# dual_vca_main.net
KiCad netlist of a schematic drawn in EAGLE
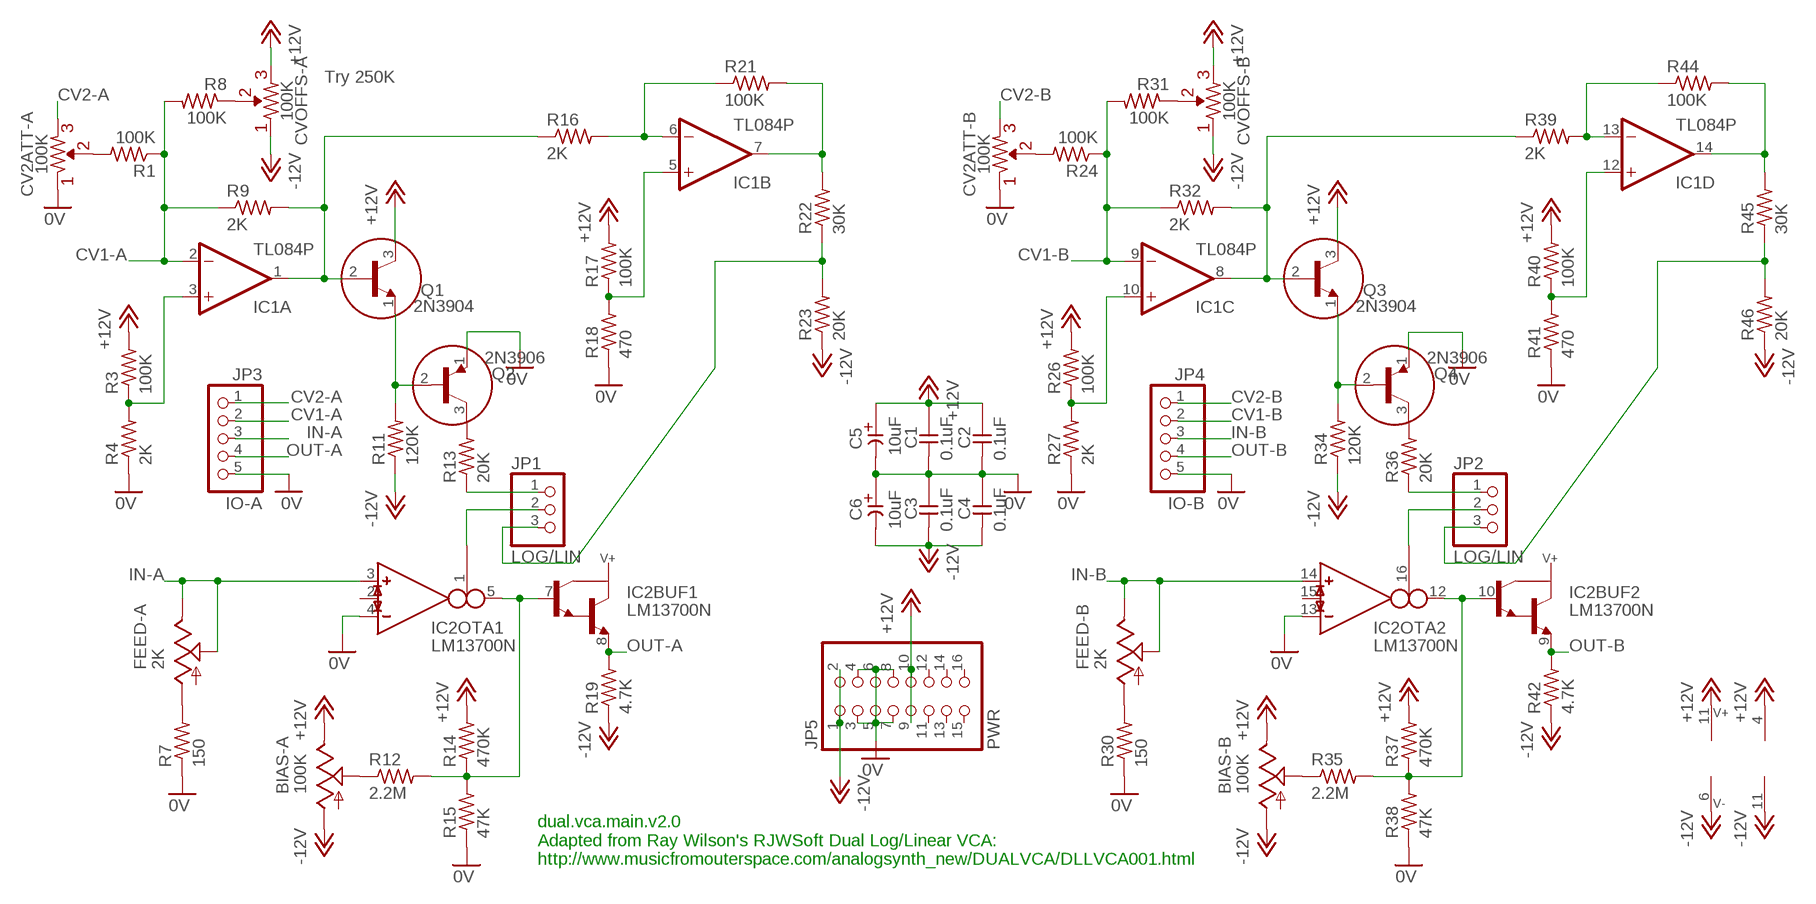
[diagram p0: schematic, sheet 1]

(export (version "E")
  (design (tool "Eeschema 10.0.6"))
  (components
    (comp (ref "BIAS-A")
      (value "100K")
      (footprint "eagle-import:PT-10S")
      (libsource (lib "eagle-import") (part "TRIM_US-PT10S"))
    )
    (comp (ref "BIAS-B")
      (value "100K")
      (footprint "eagle-import:PT-10S")
      (libsource (lib "eagle-import") (part "TRIM_US-PT10S"))
    )
    (comp (ref "C1")
      (value "0.1uF")
      (footprint "eagle-import:C025-024X044")
      (libsource (lib "eagle-import") (part "CC-US025-024X044"))
    )
    (comp (ref "C2")
      (value "0.1uF")
      (footprint "eagle-import:C025-024X044")
      (libsource (lib "eagle-import") (part "CC-US025-024X044"))
    )
    (comp (ref "C3")
      (value "0.1uF")
      (footprint "eagle-import:C025-024X044")
      (libsource (lib "eagle-import") (part "CC-US025-024X044"))
    )
    (comp (ref "C4")
      (value "0.1uF")
      (footprint "eagle-import:C025-024X044")
      (libsource (lib "eagle-import") (part "CC-US025-024X044"))
    )
    (comp (ref "C5")
      (value "10uF")
      (footprint "eagle-import:E2-5")
      (libsource (lib "eagle-import") (part "CE-USE2-5"))
    )
    (comp (ref "C6")
      (value "10uF")
      (footprint "eagle-import:E2-5")
      (libsource (lib "eagle-import") (part "CE-USE2-5"))
    )
    (comp (ref "CV2ATT-A")
      (value "100K")
      (footprint "eagle-import:R-VAR")
      (libsource (lib "eagle-import") (part "R-VAR"))
    )
    (comp (ref "CV2ATT-B")
      (value "100K")
      (footprint "eagle-import:R-VAR")
      (libsource (lib "eagle-import") (part "R-VAR"))
    )
    (comp (ref "CVOFFS-A")
      (value "100K")
      (footprint "eagle-import:R-VAR")
      (libsource (lib "eagle-import") (part "R-VAR"))
    )
    (comp (ref "CVOFFS-B")
      (value "100K")
      (footprint "eagle-import:R-VAR")
      (libsource (lib "eagle-import") (part "R-VAR"))
    )
    (comp (ref "FEED-A")
      (value "2K")
      (footprint "eagle-import:PT-10S")
      (libsource (lib "eagle-import") (part "TRIM_US-PT10S"))
    )
    (comp (ref "FEED-B")
      (value "2K")
      (footprint "eagle-import:PT-10S")
      (libsource (lib "eagle-import") (part "TRIM_US-PT10S"))
    )
    (comp (ref "IC1")
      (value "TL084P")
      (footprint "eagle-import:DIL14")
      (libsource (lib "eagle-import") (part "TL084P"))
    )
    (comp (ref "IC2")
      (value "LM13700N")
      (footprint "eagle-import:DIL16")
      (libsource (lib "eagle-import") (part "LM13700N"))
    )
    (comp (ref "JP1")
      (value "LOG/LIN")
      (footprint "eagle-import:1X03")
      (libsource (lib "eagle-import") (part "PINHD-1X3"))
    )
    (comp (ref "JP2")
      (value "LOG/LIN")
      (footprint "eagle-import:1X03")
      (libsource (lib "eagle-import") (part "PINHD-1X3"))
    )
    (comp (ref "JP3")
      (value "IO-A")
      (footprint "eagle-import:1X05")
      (libsource (lib "eagle-import") (part "PINHD-1X5"))
    )
    (comp (ref "JP4")
      (value "IO-B")
      (footprint "eagle-import:1X05")
      (libsource (lib "eagle-import") (part "PINHD-1X5"))
    )
    (comp (ref "JP5")
      (value "PWR")
      (footprint "eagle-import:2X08")
      (libsource (lib "eagle-import") (part "PINHD-2X8"))
    )
    (comp (ref "Q1")
      (value "2N3904")
      (footprint "eagle-import:TO92")
      (libsource (lib "eagle-import") (part "2N3904"))
    )
    (comp (ref "Q2")
      (value "2N3906")
      (footprint "eagle-import:TO92")
      (libsource (lib "eagle-import") (part "2N3906"))
    )
    (comp (ref "Q3")
      (value "2N3904")
      (footprint "eagle-import:TO92")
      (libsource (lib "eagle-import") (part "2N3904"))
    )
    (comp (ref "Q4")
      (value "2N3906")
      (footprint "eagle-import:TO92")
      (libsource (lib "eagle-import") (part "2N3906"))
    )
    (comp (ref "R1")
      (value "100K")
      (footprint "eagle-import:0207_7")
      (libsource (lib "eagle-import") (part "R-US_0207/7"))
    )
    (comp (ref "R3")
      (value "100K")
      (footprint "eagle-import:0207_7")
      (libsource (lib "eagle-import") (part "R-US_0207/7"))
    )
    (comp (ref "R4")
      (value "2K")
      (footprint "eagle-import:0207_7")
      (libsource (lib "eagle-import") (part "R-US_0207/7"))
    )
    (comp (ref "R7")
      (value "150")
      (footprint "eagle-import:0207_7")
      (libsource (lib "eagle-import") (part "R-US_0207/7"))
    )
    (comp (ref "R8")
      (value "100K")
      (footprint "eagle-import:0207_7")
      (libsource (lib "eagle-import") (part "R-US_0207/7"))
    )
    (comp (ref "R9")
      (value "2K")
      (footprint "eagle-import:0207_7")
      (libsource (lib "eagle-import") (part "R-US_0207/7"))
    )
    (comp (ref "R11")
      (value "120K")
      (footprint "eagle-import:0207_7")
      (libsource (lib "eagle-import") (part "R-US_0207/7"))
    )
    (comp (ref "R12")
      (value "2.2M")
      (footprint "eagle-import:0207_7")
      (libsource (lib "eagle-import") (part "R-US_0207/7"))
    )
    (comp (ref "R13")
      (value "20K")
      (footprint "eagle-import:0207_7")
      (libsource (lib "eagle-import") (part "R-US_0207/7"))
    )
    (comp (ref "R14")
      (value "470K")
      (footprint "eagle-import:0207_7")
      (libsource (lib "eagle-import") (part "R-US_0207/7"))
    )
    (comp (ref "R15")
      (value "47K")
      (footprint "eagle-import:0207_7")
      (libsource (lib "eagle-import") (part "R-US_0207/7"))
    )
    (comp (ref "R16")
      (value "2K")
      (footprint "eagle-import:0207_7")
      (libsource (lib "eagle-import") (part "R-US_0207/7"))
    )
    (comp (ref "R17")
      (value "100K")
      (footprint "eagle-import:0207_7")
      (libsource (lib "eagle-import") (part "R-US_0207/7"))
    )
    (comp (ref "R18")
      (value "470")
      (footprint "eagle-import:0207_7")
      (libsource (lib "eagle-import") (part "R-US_0207/7"))
    )
    (comp (ref "R19")
      (value "4.7K")
      (footprint "eagle-import:0207_7")
      (libsource (lib "eagle-import") (part "R-US_0207/7"))
    )
    (comp (ref "R21")
      (value "100K")
      (footprint "eagle-import:0207_7")
      (libsource (lib "eagle-import") (part "R-US_0207/7"))
    )
    (comp (ref "R22")
      (value "30K")
      (footprint "eagle-import:0207_7")
      (libsource (lib "eagle-import") (part "R-US_0207/7"))
    )
    (comp (ref "R23")
      (value "20K")
      (footprint "eagle-import:0207_7")
      (libsource (lib "eagle-import") (part "R-US_0207/7"))
    )
    (comp (ref "R24")
      (value "100K")
      (footprint "eagle-import:0207_7")
      (libsource (lib "eagle-import") (part "R-US_0207/7"))
    )
    (comp (ref "R26")
      (value "100K")
      (footprint "eagle-import:0207_7")
      (libsource (lib "eagle-import") (part "R-US_0207/7"))
    )
    (comp (ref "R27")
      (value "2K")
      (footprint "eagle-import:0207_7")
      (libsource (lib "eagle-import") (part "R-US_0207/7"))
    )
    (comp (ref "R30")
      (value "150")
      (footprint "eagle-import:0207_7")
      (libsource (lib "eagle-import") (part "R-US_0207/7"))
    )
    (comp (ref "R31")
      (value "100K")
      (footprint "eagle-import:0207_7")
      (libsource (lib "eagle-import") (part "R-US_0207/7"))
    )
    (comp (ref "R32")
      (value "2K")
      (footprint "eagle-import:0207_7")
      (libsource (lib "eagle-import") (part "R-US_0207/7"))
    )
    (comp (ref "R34")
      (value "120K")
      (footprint "eagle-import:0207_7")
      (libsource (lib "eagle-import") (part "R-US_0207/7"))
    )
    (comp (ref "R35")
      (value "2.2M")
      (footprint "eagle-import:0207_7")
      (libsource (lib "eagle-import") (part "R-US_0207/7"))
    )
    (comp (ref "R36")
      (value "20K")
      (footprint "eagle-import:0207_7")
      (libsource (lib "eagle-import") (part "R-US_0207/7"))
    )
    (comp (ref "R37")
      (value "470K")
      (footprint "eagle-import:0207_7")
      (libsource (lib "eagle-import") (part "R-US_0207/7"))
    )
    (comp (ref "R38")
      (value "47K")
      (footprint "eagle-import:0207_7")
      (libsource (lib "eagle-import") (part "R-US_0207/7"))
    )
    (comp (ref "R39")
      (value "2K")
      (footprint "eagle-import:0207_7")
      (libsource (lib "eagle-import") (part "R-US_0207/7"))
    )
    (comp (ref "R40")
      (value "100K")
      (footprint "eagle-import:0207_7")
      (libsource (lib "eagle-import") (part "R-US_0207/7"))
    )
    (comp (ref "R41")
      (value "470")
      (footprint "eagle-import:0207_7")
      (libsource (lib "eagle-import") (part "R-US_0207/7"))
    )
    (comp (ref "R42")
      (value "4.7K")
      (footprint "eagle-import:0207_7")
      (libsource (lib "eagle-import") (part "R-US_0207/7"))
    )
    (comp (ref "R44")
      (value "100K")
      (footprint "eagle-import:0207_7")
      (libsource (lib "eagle-import") (part "R-US_0207/7"))
    )
    (comp (ref "R45")
      (value "30K")
      (footprint "eagle-import:0207_7")
      (libsource (lib "eagle-import") (part "R-US_0207/7"))
    )
    (comp (ref "R46")
      (value "20K")
      (footprint "eagle-import:0207_7")
      (libsource (lib "eagle-import") (part "R-US_0207/7"))
    )
  )
  (nets
    (net (code "1") (name "+12V") (class "Default")
      (node (ref "BIAS-A") (pin "E") (pinfunction "E_E") (pintype "passive"))
      (node (ref "BIAS-B") (pin "E") (pinfunction "E_E") (pintype "passive"))
      (node (ref "C1") (pin "1") (pinfunction "1_1") (pintype "passive"))
      (node (ref "C2") (pin "1") (pinfunction "1_1") (pintype "passive"))
      (node (ref "C5") (pin "+") (pinfunction "+_+") (pintype "passive"))
      (node (ref "CVOFFS-A") (pin "R2") (pinfunction "2_R2") (pintype "passive"))
      (node (ref "CVOFFS-B") (pin "R2") (pinfunction "2_R2") (pintype "passive"))
      (node (ref "IC1") (pin "4") (pinfunction "V+_4") (pintype "power_in"))
      (node (ref "IC2") (pin "11") (pinfunction "V+_11") (pintype "power_in"))
      (node (ref "JP5") (pin "10") (pinfunction "10_10") (pintype "passive"))
      (node (ref "JP5") (pin "9") (pinfunction "9_9") (pintype "passive"))
      (node (ref "Q1") (pin "3") (pinfunction "C_3") (pintype "passive"))
      (node (ref "Q3") (pin "3") (pinfunction "C_3") (pintype "passive"))
      (node (ref "R14") (pin "2") (pinfunction "2_2") (pintype "passive"))
      (node (ref "R17") (pin "2") (pinfunction "2_2") (pintype "passive"))
      (node (ref "R26") (pin "2") (pinfunction "2_2") (pintype "passive"))
      (node (ref "R3") (pin "2") (pinfunction "2_2") (pintype "passive"))
      (node (ref "R37") (pin "2") (pinfunction "2_2") (pintype "passive"))
      (node (ref "R40") (pin "2") (pinfunction "2_2") (pintype "passive"))
    )
    (net (code "2") (name "-12V") (class "Default")
      (node (ref "BIAS-A") (pin "A") (pinfunction "A_A") (pintype "passive"))
      (node (ref "BIAS-B") (pin "A") (pinfunction "A_A") (pintype "passive"))
      (node (ref "C3") (pin "2") (pinfunction "2_2") (pintype "passive"))
      (node (ref "C4") (pin "2") (pinfunction "2_2") (pintype "passive"))
      (node (ref "C6") (pin "-") (pinfunction "-_-") (pintype "passive"))
      (node (ref "CVOFFS-A") (pin "R1") (pinfunction "1_R1") (pintype "passive"))
      (node (ref "CVOFFS-B") (pin "R1") (pinfunction "1_R1") (pintype "passive"))
      (node (ref "IC1") (pin "11") (pinfunction "V-_11") (pintype "power_in"))
      (node (ref "IC2") (pin "6") (pinfunction "V-_6") (pintype "power_in"))
      (node (ref "JP5") (pin "1") (pinfunction "1_1") (pintype "passive"))
      (node (ref "JP5") (pin "2") (pinfunction "2_2") (pintype "passive"))
      (node (ref "R11") (pin "1") (pinfunction "1_1") (pintype "passive"))
      (node (ref "R19") (pin "1") (pinfunction "1_1") (pintype "passive"))
      (node (ref "R23") (pin "1") (pinfunction "1_1") (pintype "passive"))
      (node (ref "R34") (pin "1") (pinfunction "1_1") (pintype "passive"))
      (node (ref "R42") (pin "1") (pinfunction "1_1") (pintype "passive"))
      (node (ref "R46") (pin "1") (pinfunction "1_1") (pintype "passive"))
    )
    (net (code "3") (name "/CV1-A") (class "Default")
      (node (ref "IC1") (pin "2") (pinfunction "-IN_2") (pintype "input"))
      (node (ref "JP3") (pin "2") (pinfunction "2_2") (pintype "passive"))
      (node (ref "R1") (pin "1") (pinfunction "1_1") (pintype "passive"))
      (node (ref "R8") (pin "2") (pinfunction "2_2") (pintype "passive"))
      (node (ref "R9") (pin "1") (pinfunction "1_1") (pintype "passive"))
    )
    (net (code "4") (name "/CV1-B") (class "Default")
      (node (ref "IC1") (pin "9") (pinfunction "-IN_9") (pintype "input"))
      (node (ref "JP4") (pin "2") (pinfunction "2_2") (pintype "passive"))
      (node (ref "R24") (pin "1") (pinfunction "1_1") (pintype "passive"))
      (node (ref "R31") (pin "2") (pinfunction "2_2") (pintype "passive"))
      (node (ref "R32") (pin "1") (pinfunction "1_1") (pintype "passive"))
    )
    (net (code "5") (name "/CV2-A") (class "Default")
      (node (ref "CV2ATT-A") (pin "R2") (pinfunction "2_R2") (pintype "passive"))
      (node (ref "JP3") (pin "1") (pinfunction "1_1") (pintype "passive"))
    )
    (net (code "6") (name "/CV2-B") (class "Default")
      (node (ref "CV2ATT-B") (pin "R2") (pinfunction "2_R2") (pintype "passive"))
      (node (ref "JP4") (pin "1") (pinfunction "1_1") (pintype "passive"))
    )
    (net (code "7") (name "/IN-A") (class "Default")
      (node (ref "FEED-A") (pin "E") (pinfunction "E_E") (pintype "passive"))
      (node (ref "FEED-A") (pin "S") (pinfunction "S_S") (pintype "passive"))
      (node (ref "IC2") (pin "3") (pinfunction "IN_P_3") (pintype "input"))
      (node (ref "JP3") (pin "3") (pinfunction "3_3") (pintype "passive"))
    )
    (net (code "8") (name "/IN-B") (class "Default")
      (node (ref "FEED-B") (pin "E") (pinfunction "E_E") (pintype "passive"))
      (node (ref "FEED-B") (pin "S") (pinfunction "S_S") (pintype "passive"))
      (node (ref "IC2") (pin "14") (pinfunction "IN_P_14") (pintype "input"))
      (node (ref "JP4") (pin "3") (pinfunction "3_3") (pintype "passive"))
    )
    (net (code "9") (name "/OUT-A") (class "Default")
      (node (ref "IC2") (pin "8") (pinfunction "E_8") (pintype "passive"))
      (node (ref "JP3") (pin "4") (pinfunction "4_4") (pintype "passive"))
      (node (ref "R19") (pin "2") (pinfunction "2_2") (pintype "passive"))
    )
    (net (code "10") (name "/OUT-B") (class "Default")
      (node (ref "IC2") (pin "9") (pinfunction "E_9") (pintype "passive"))
      (node (ref "JP4") (pin "4") (pinfunction "4_4") (pintype "passive"))
      (node (ref "R42") (pin "2") (pinfunction "2_2") (pintype "passive"))
    )
    (net (code "11") (name "0V") (class "Default")
      (node (ref "C1") (pin "2") (pinfunction "2_2") (pintype "passive"))
      (node (ref "C2") (pin "2") (pinfunction "2_2") (pintype "passive"))
      (node (ref "C3") (pin "1") (pinfunction "1_1") (pintype "passive"))
      (node (ref "C4") (pin "1") (pinfunction "1_1") (pintype "passive"))
      (node (ref "C5") (pin "-") (pinfunction "-_-") (pintype "passive"))
      (node (ref "C6") (pin "+") (pinfunction "+_+") (pintype "passive"))
      (node (ref "CV2ATT-A") (pin "R1") (pinfunction "1_R1") (pintype "passive"))
      (node (ref "CV2ATT-B") (pin "R1") (pinfunction "1_R1") (pintype "passive"))
      (node (ref "IC2") (pin "13") (pinfunction "IN_N_13") (pintype "input"))
      (node (ref "IC2") (pin "4") (pinfunction "IN_N_4") (pintype "input"))
      (node (ref "JP3") (pin "5") (pinfunction "5_5") (pintype "passive"))
      (node (ref "JP4") (pin "5") (pinfunction "5_5") (pintype "passive"))
      (node (ref "JP5") (pin "3") (pinfunction "3_3") (pintype "passive"))
      (node (ref "JP5") (pin "4") (pinfunction "4_4") (pintype "passive"))
      (node (ref "JP5") (pin "5") (pinfunction "5_5") (pintype "passive"))
      (node (ref "JP5") (pin "6") (pinfunction "6_6") (pintype "passive"))
      (node (ref "JP5") (pin "7") (pinfunction "7_7") (pintype "passive"))
      (node (ref "JP5") (pin "8") (pinfunction "8_8") (pintype "passive"))
      (node (ref "Q2") (pin "1") (pinfunction "E_1") (pintype "passive"))
      (node (ref "Q4") (pin "1") (pinfunction "E_1") (pintype "passive"))
      (node (ref "R15") (pin "1") (pinfunction "1_1") (pintype "passive"))
      (node (ref "R18") (pin "1") (pinfunction "1_1") (pintype "passive"))
      (node (ref "R27") (pin "1") (pinfunction "1_1") (pintype "passive"))
      (node (ref "R30") (pin "1") (pinfunction "1_1") (pintype "passive"))
      (node (ref "R38") (pin "1") (pinfunction "1_1") (pintype "passive"))
      (node (ref "R4") (pin "1") (pinfunction "1_1") (pintype "passive"))
      (node (ref "R41") (pin "1") (pinfunction "1_1") (pintype "passive"))
      (node (ref "R7") (pin "1") (pinfunction "1_1") (pintype "passive"))
    )
    (net (code "12") (name "Net-(BIAS-A-PadS)") (class "Default")
      (node (ref "BIAS-A") (pin "S") (pinfunction "S_S") (pintype "passive"))
      (node (ref "R12") (pin "1") (pinfunction "1_1") (pintype "passive"))
    )
    (net (code "13") (name "Net-(BIAS-B-PadS)") (class "Default")
      (node (ref "BIAS-B") (pin "S") (pinfunction "S_S") (pintype "passive"))
      (node (ref "R35") (pin "1") (pinfunction "1_1") (pintype "passive"))
    )
    (net (code "14") (name "Net-(CV2ATT-A-P$1)") (class "Default")
      (node (ref "CV2ATT-A") (pin "VAR") (pinfunction "P$1_VAR") (pintype "passive"))
      (node (ref "R1") (pin "2") (pinfunction "2_2") (pintype "passive"))
    )
    (net (code "15") (name "Net-(CV2ATT-B-P$1)") (class "Default")
      (node (ref "CV2ATT-B") (pin "VAR") (pinfunction "P$1_VAR") (pintype "passive"))
      (node (ref "R24") (pin "2") (pinfunction "2_2") (pintype "passive"))
    )
    (net (code "16") (name "Net-(CVOFFS-A-P$1)") (class "Default")
      (node (ref "CVOFFS-A") (pin "VAR") (pinfunction "P$1_VAR") (pintype "passive"))
      (node (ref "R8") (pin "1") (pinfunction "1_1") (pintype "passive"))
    )
    (net (code "17") (name "Net-(CVOFFS-B-P$1)") (class "Default")
      (node (ref "CVOFFS-B") (pin "VAR") (pinfunction "P$1_VAR") (pintype "passive"))
      (node (ref "R31") (pin "1") (pinfunction "1_1") (pintype "passive"))
    )
    (net (code "18") (name "Net-(FEED-A-PadA)") (class "Default")
      (node (ref "FEED-A") (pin "A") (pinfunction "A_A") (pintype "passive"))
      (node (ref "R7") (pin "2") (pinfunction "2_2") (pintype "passive"))
    )
    (net (code "19") (name "Net-(FEED-B-PadA)") (class "Default")
      (node (ref "FEED-B") (pin "A") (pinfunction "A_A") (pintype "passive"))
      (node (ref "R30") (pin "2") (pinfunction "2_2") (pintype "passive"))
    )
    (net (code "20") (name "Net-(IC1A-+IN)") (class "Default")
      (node (ref "IC1") (pin "3") (pinfunction "+IN_3") (pintype "input"))
      (node (ref "R3") (pin "1") (pinfunction "1_1") (pintype "passive"))
      (node (ref "R4") (pin "2") (pinfunction "2_2") (pintype "passive"))
    )
    (net (code "21") (name "Net-(IC1A-OUT)") (class "Default")
      (node (ref "IC1") (pin "1") (pinfunction "OUT_1") (pintype "output"))
      (node (ref "Q1") (pin "2") (pinfunction "B_2") (pintype "passive"))
      (node (ref "R16") (pin "1") (pinfunction "1_1") (pintype "passive"))
      (node (ref "R9") (pin "2") (pinfunction "2_2") (pintype "passive"))
    )
    (net (code "22") (name "Net-(IC1B-+IN)") (class "Default")
      (node (ref "IC1") (pin "5") (pinfunction "+IN_5") (pintype "input"))
      (node (ref "R17") (pin "1") (pinfunction "1_1") (pintype "passive"))
      (node (ref "R18") (pin "2") (pinfunction "2_2") (pintype "passive"))
    )
    (net (code "23") (name "Net-(IC1B--IN)") (class "Default")
      (node (ref "IC1") (pin "6") (pinfunction "-IN_6") (pintype "input"))
      (node (ref "R16") (pin "2") (pinfunction "2_2") (pintype "passive"))
      (node (ref "R21") (pin "1") (pinfunction "1_1") (pintype "passive"))
    )
    (net (code "24") (name "Net-(IC1B-OUT)") (class "Default")
      (node (ref "IC1") (pin "7") (pinfunction "OUT_7") (pintype "output"))
      (node (ref "R21") (pin "2") (pinfunction "2_2") (pintype "passive"))
      (node (ref "R22") (pin "2") (pinfunction "2_2") (pintype "passive"))
    )
    (net (code "25") (name "Net-(IC1C-+IN)") (class "Default")
      (node (ref "IC1") (pin "10") (pinfunction "+IN_10") (pintype "input"))
      (node (ref "R26") (pin "1") (pinfunction "1_1") (pintype "passive"))
      (node (ref "R27") (pin "2") (pinfunction "2_2") (pintype "passive"))
    )
    (net (code "26") (name "Net-(IC1C-OUT)") (class "Default")
      (node (ref "IC1") (pin "8") (pinfunction "OUT_8") (pintype "output"))
      (node (ref "Q3") (pin "2") (pinfunction "B_2") (pintype "passive"))
      (node (ref "R32") (pin "2") (pinfunction "2_2") (pintype "passive"))
      (node (ref "R39") (pin "1") (pinfunction "1_1") (pintype "passive"))
    )
    (net (code "27") (name "Net-(IC1D-+IN)") (class "Default")
      (node (ref "IC1") (pin "12") (pinfunction "+IN_12") (pintype "input"))
      (node (ref "R40") (pin "1") (pinfunction "1_1") (pintype "passive"))
      (node (ref "R41") (pin "2") (pinfunction "2_2") (pintype "passive"))
    )
    (net (code "28") (name "Net-(IC1D--IN)") (class "Default")
      (node (ref "IC1") (pin "13") (pinfunction "-IN_13") (pintype "input"))
      (node (ref "R39") (pin "2") (pinfunction "2_2") (pintype "passive"))
      (node (ref "R44") (pin "1") (pinfunction "1_1") (pintype "passive"))
    )
    (net (code "29") (name "Net-(IC1D-OUT)") (class "Default")
      (node (ref "IC1") (pin "14") (pinfunction "OUT_14") (pintype "output"))
      (node (ref "R44") (pin "2") (pinfunction "2_2") (pintype "passive"))
      (node (ref "R45") (pin "2") (pinfunction "2_2") (pintype "passive"))
    )
    (net (code "30") (name "Net-(IC2A-B)") (class "Default")
      (node (ref "IC2") (pin "5") (pinfunction "OUT_5") (pintype "output"))
      (node (ref "IC2") (pin "7") (pinfunction "B_7") (pintype "passive"))
      (node (ref "R12") (pin "2") (pinfunction "2_2") (pintype "passive"))
      (node (ref "R14") (pin "1") (pinfunction "1_1") (pintype "passive"))
      (node (ref "R15") (pin "2") (pinfunction "2_2") (pintype "passive"))
    )
    (net (code "31") (name "Net-(IC2B-B)") (class "Default")
      (node (ref "IC2") (pin "10") (pinfunction "B_10") (pintype "passive"))
      (node (ref "IC2") (pin "12") (pinfunction "OUT_12") (pintype "output"))
      (node (ref "R35") (pin "2") (pinfunction "2_2") (pintype "passive"))
      (node (ref "R37") (pin "1") (pinfunction "1_1") (pintype "passive"))
      (node (ref "R38") (pin "2") (pinfunction "2_2") (pintype "passive"))
    )
    (net (code "32") (name "Net-(IC2C-I_BIAS)") (class "Default")
      (node (ref "IC2") (pin "1") (pinfunction "I_BIAS_1") (pintype "input"))
      (node (ref "JP1") (pin "2") (pinfunction "2_2") (pintype "passive"))
    )
    (net (code "33") (name "Net-(IC2D-I_BIAS)") (class "Default")
      (node (ref "IC2") (pin "16") (pinfunction "I_BIAS_16") (pintype "input"))
      (node (ref "JP2") (pin "2") (pinfunction "2_2") (pintype "passive"))
    )
    (net (code "34") (name "Net-(JP1-Pad1)") (class "Default")
      (node (ref "JP1") (pin "1") (pinfunction "1_1") (pintype "passive"))
      (node (ref "R13") (pin "1") (pinfunction "1_1") (pintype "passive"))
    )
    (net (code "35") (name "Net-(JP1-Pad3)") (class "Default")
      (node (ref "JP1") (pin "3") (pinfunction "3_3") (pintype "passive"))
      (node (ref "R22") (pin "1") (pinfunction "1_1") (pintype "passive"))
      (node (ref "R23") (pin "2") (pinfunction "2_2") (pintype "passive"))
    )
    (net (code "36") (name "Net-(JP2-Pad1)") (class "Default")
      (node (ref "JP2") (pin "1") (pinfunction "1_1") (pintype "passive"))
      (node (ref "R36") (pin "1") (pinfunction "1_1") (pintype "passive"))
    )
    (net (code "37") (name "Net-(JP2-Pad3)") (class "Default")
      (node (ref "JP2") (pin "3") (pinfunction "3_3") (pintype "passive"))
      (node (ref "R45") (pin "1") (pinfunction "1_1") (pintype "passive"))
      (node (ref "R46") (pin "2") (pinfunction "2_2") (pintype "passive"))
    )
    (net (code "38") (name "Net-(Q1-E)") (class "Default")
      (node (ref "Q1") (pin "1") (pinfunction "E_1") (pintype "passive"))
      (node (ref "Q2") (pin "2") (pinfunction "B_2") (pintype "passive"))
      (node (ref "R11") (pin "2") (pinfunction "2_2") (pintype "passive"))
    )
    (net (code "39") (name "Net-(Q2-C)") (class "Default")
      (node (ref "Q2") (pin "3") (pinfunction "C_3") (pintype "passive"))
      (node (ref "R13") (pin "2") (pinfunction "2_2") (pintype "passive"))
    )
    (net (code "40") (name "Net-(Q3-E)") (class "Default")
      (node (ref "Q3") (pin "1") (pinfunction "E_1") (pintype "passive"))
      (node (ref "Q4") (pin "2") (pinfunction "B_2") (pintype "passive"))
      (node (ref "R34") (pin "2") (pinfunction "2_2") (pintype "passive"))
    )
    (net (code "41") (name "Net-(Q4-C)") (class "Default")
      (node (ref "Q4") (pin "3") (pinfunction "C_3") (pintype "passive"))
      (node (ref "R36") (pin "2") (pinfunction "2_2") (pintype "passive"))
    )
    (net (code "42") (name "unconnected-(IC2C-I_DIODE-Pad2)") (class "Default")
      (node (ref "IC2") (pin "2") (pinfunction "I_DIODE_2") (pintype "input"))
    )
    (net (code "43") (name "unconnected-(IC2D-I_DIODE-Pad15)") (class "Default")
      (node (ref "IC2") (pin "15") (pinfunction "I_DIODE_15") (pintype "input"))
    )
    (net (code "44") (name "unconnected-(JP5-Pad11)") (class "Default")
      (node (ref "JP5") (pin "11") (pinfunction "11_11") (pintype "passive"))
    )
    (net (code "45") (name "unconnected-(JP5-Pad12)") (class "Default")
      (node (ref "JP5") (pin "12") (pinfunction "12_12") (pintype "passive"))
    )
    (net (code "46") (name "unconnected-(JP5-Pad13)") (class "Default")
      (node (ref "JP5") (pin "13") (pinfunction "13_13") (pintype "passive"))
    )
    (net (code "47") (name "unconnected-(JP5-Pad14)") (class "Default")
      (node (ref "JP5") (pin "14") (pinfunction "14_14") (pintype "passive"))
    )
    (net (code "48") (name "unconnected-(JP5-Pad15)") (class "Default")
      (node (ref "JP5") (pin "15") (pinfunction "15_15") (pintype "passive"))
    )
    (net (code "49") (name "unconnected-(JP5-Pad16)") (class "Default")
      (node (ref "JP5") (pin "16") (pinfunction "16_16") (pintype "passive"))
    )
  )
)
